# sunhub8_v1_0.net
KiCad netlist of a schematic drawn in EAGLE
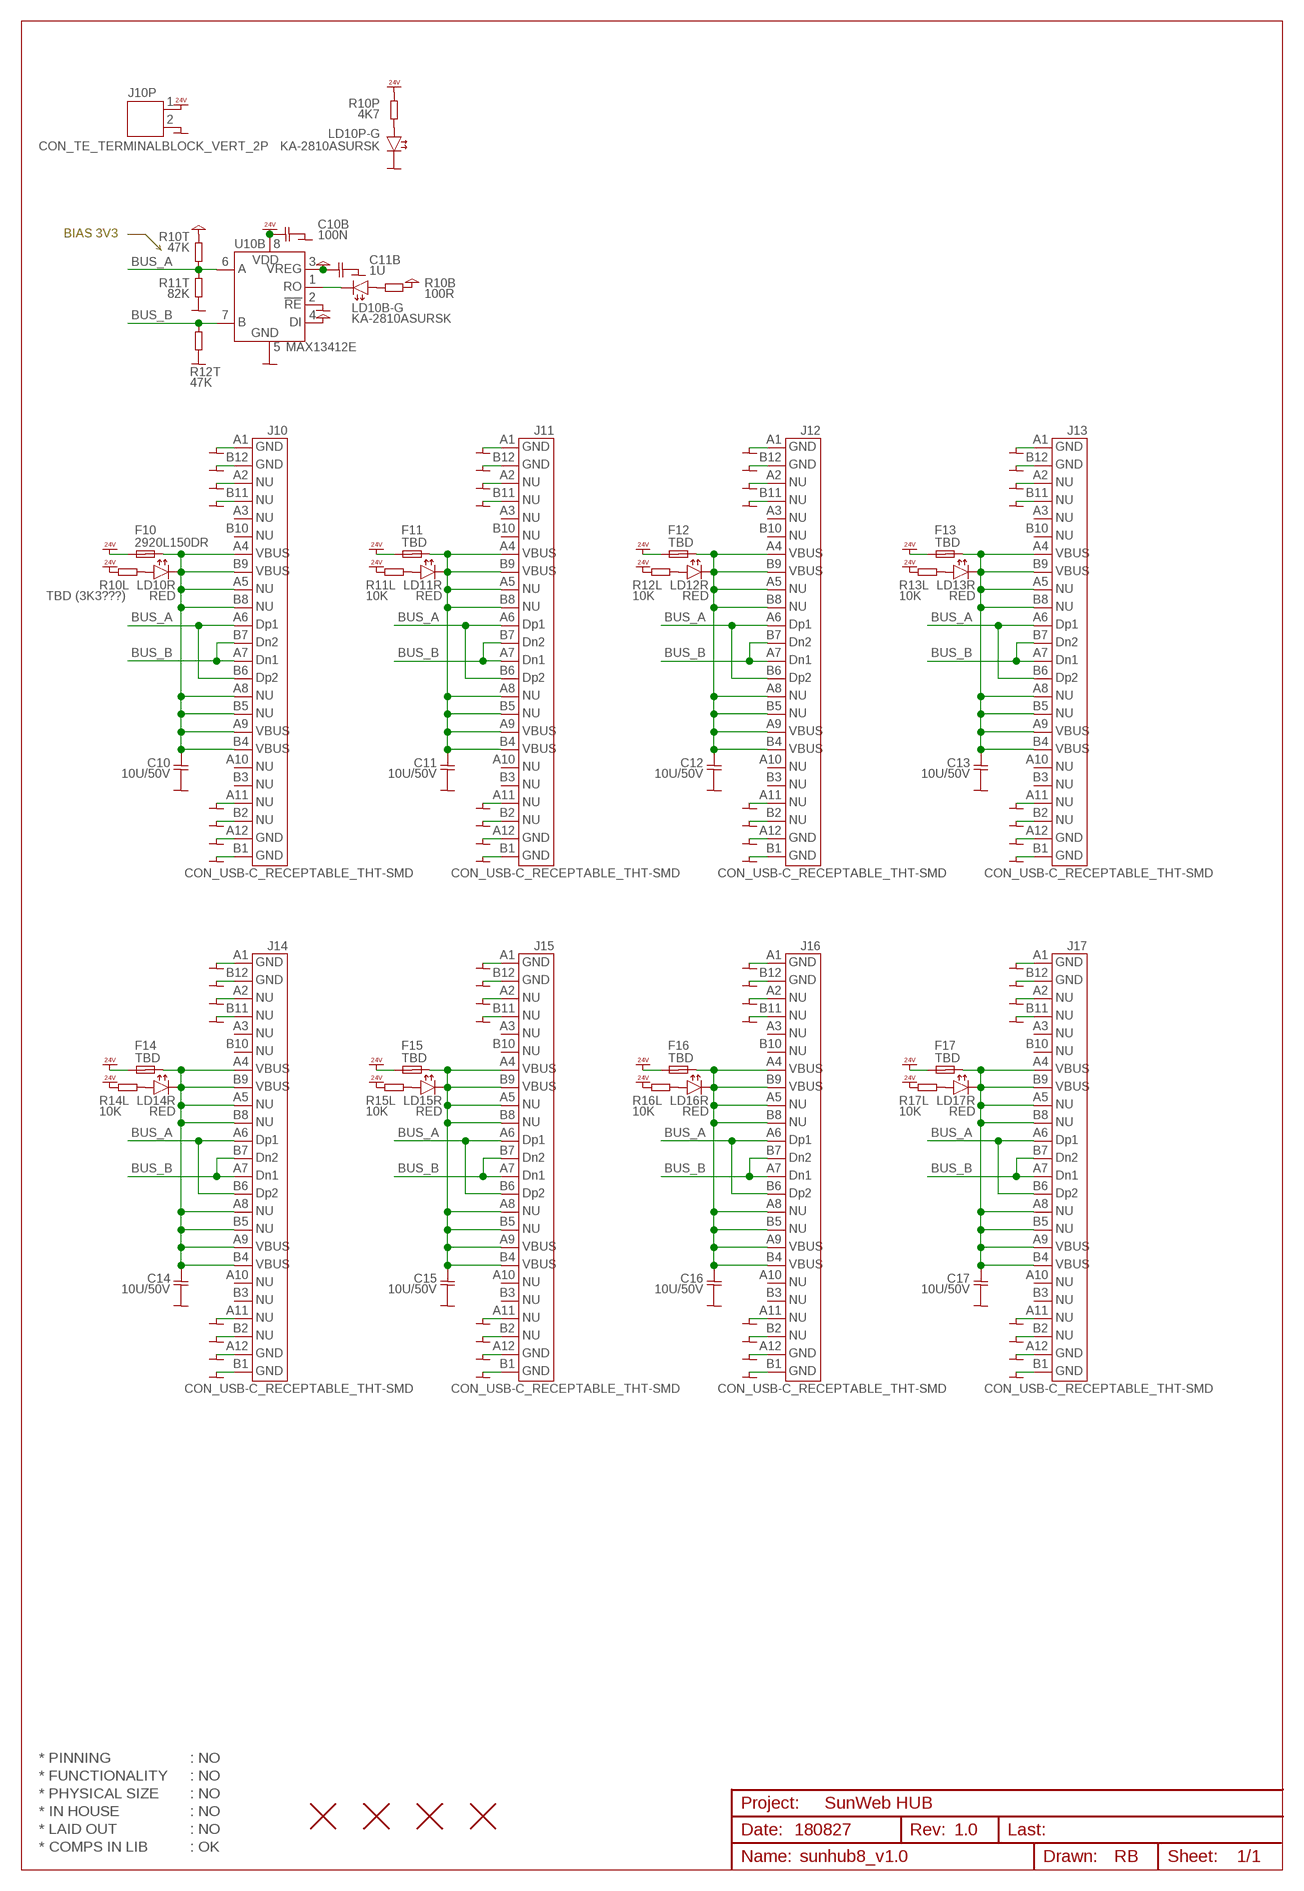
[diagram p0: schematic, sheet 1]

(export (version "E")
  (design (tool "Eeschema 10.0.6"))
  (components
    (comp (ref "C10")
      (value "10U/50V")
      (footprint "eagle-import:CAP1206")
      (libsource (lib "eagle-import") (part "CAP1206"))
    )
    (comp (ref "C10B")
      (value "100N")
      (footprint "eagle-import:CAP0603")
      (libsource (lib "eagle-import") (part "CAP0603"))
    )
    (comp (ref "C11")
      (value "10U/50V")
      (footprint "eagle-import:CAP1206")
      (libsource (lib "eagle-import") (part "CAP1206"))
    )
    (comp (ref "C11B")
      (value "1U")
      (footprint "eagle-import:CAP0603")
      (libsource (lib "eagle-import") (part "CAP0603"))
    )
    (comp (ref "C12")
      (value "10U/50V")
      (footprint "eagle-import:CAP1206")
      (libsource (lib "eagle-import") (part "CAP1206"))
    )
    (comp (ref "C13")
      (value "10U/50V")
      (footprint "eagle-import:CAP1206")
      (libsource (lib "eagle-import") (part "CAP1206"))
    )
    (comp (ref "C14")
      (value "10U/50V")
      (footprint "eagle-import:CAP1206")
      (libsource (lib "eagle-import") (part "CAP1206"))
    )
    (comp (ref "C15")
      (value "10U/50V")
      (footprint "eagle-import:CAP1206")
      (libsource (lib "eagle-import") (part "CAP1206"))
    )
    (comp (ref "C16")
      (value "10U/50V")
      (footprint "eagle-import:CAP1206")
      (libsource (lib "eagle-import") (part "CAP1206"))
    )
    (comp (ref "C17")
      (value "10U/50V")
      (footprint "eagle-import:CAP1206")
      (libsource (lib "eagle-import") (part "CAP1206"))
    )
    (comp (ref "F10")
      (value "2920L150DR")
      (footprint "eagle-import:POLYFUSE2920")
      (libsource (lib "eagle-import") (part "POLYFUSE2920"))
    )
    (comp (ref "F11")
      (value "TBD")
      (footprint "eagle-import:POLYFUSE2920")
      (libsource (lib "eagle-import") (part "POLYFUSE2920"))
    )
    (comp (ref "F12")
      (value "TBD")
      (footprint "eagle-import:POLYFUSE2920")
      (libsource (lib "eagle-import") (part "POLYFUSE2920"))
    )
    (comp (ref "F13")
      (value "TBD")
      (footprint "eagle-import:POLYFUSE2920")
      (libsource (lib "eagle-import") (part "POLYFUSE2920"))
    )
    (comp (ref "F14")
      (value "TBD")
      (footprint "eagle-import:POLYFUSE2920")
      (libsource (lib "eagle-import") (part "POLYFUSE2920"))
    )
    (comp (ref "F15")
      (value "TBD")
      (footprint "eagle-import:POLYFUSE2920")
      (libsource (lib "eagle-import") (part "POLYFUSE2920"))
    )
    (comp (ref "F16")
      (value "TBD")
      (footprint "eagle-import:POLYFUSE2920")
      (libsource (lib "eagle-import") (part "POLYFUSE2920"))
    )
    (comp (ref "F17")
      (value "TBD")
      (footprint "eagle-import:POLYFUSE2920")
      (libsource (lib "eagle-import") (part "POLYFUSE2920"))
    )
    (comp (ref "H1")
      (value "HOLE_NPTH_3.2MM")
      (footprint "eagle-import:HOLE_NPTH_3.2MM")
      (libsource (lib "eagle-import") (part "HOLE_NPTH_3.2MM"))
    )
    (comp (ref "H2")
      (value "HOLE_NPTH_3.2MM")
      (footprint "eagle-import:HOLE_NPTH_3.2MM")
      (libsource (lib "eagle-import") (part "HOLE_NPTH_3.2MM"))
    )
    (comp (ref "H3")
      (value "HOLE_NPTH_3.2MM")
      (footprint "eagle-import:HOLE_NPTH_3.2MM")
      (libsource (lib "eagle-import") (part "HOLE_NPTH_3.2MM"))
    )
    (comp (ref "H4")
      (value "HOLE_NPTH_3.2MM")
      (footprint "eagle-import:HOLE_NPTH_3.2MM")
      (libsource (lib "eagle-import") (part "HOLE_NPTH_3.2MM"))
    )
    (comp (ref "J10")
      (value "CON_USB-C_RECEPTABLE_THT-SMD")
      (footprint "eagle-import:CON_USB-C_RECEPTABLE_THT-SMD")
      (libsource (lib "eagle-import") (part "CON_USB-C_RECEPTABLE_THT-SMD"))
    )
    (comp (ref "J10P")
      (value "CON_TE_TERMINALBLOCK_VERT_2P")
      (footprint "eagle-import:CON_TE_TERMINALBLOCK_VERT_2P")
      (libsource (lib "eagle-import") (part "CON_TE_TERMINALBLOCK_VERT_2P"))
    )
    (comp (ref "J11")
      (value "CON_USB-C_RECEPTABLE_THT-SMD")
      (footprint "eagle-import:CON_USB-C_RECEPTABLE_THT-SMD")
      (libsource (lib "eagle-import") (part "CON_USB-C_RECEPTABLE_THT-SMD"))
    )
    (comp (ref "J12")
      (value "CON_USB-C_RECEPTABLE_THT-SMD")
      (footprint "eagle-import:CON_USB-C_RECEPTABLE_THT-SMD")
      (libsource (lib "eagle-import") (part "CON_USB-C_RECEPTABLE_THT-SMD"))
    )
    (comp (ref "J13")
      (value "CON_USB-C_RECEPTABLE_THT-SMD")
      (footprint "eagle-import:CON_USB-C_RECEPTABLE_THT-SMD")
      (libsource (lib "eagle-import") (part "CON_USB-C_RECEPTABLE_THT-SMD"))
    )
    (comp (ref "J14")
      (value "CON_USB-C_RECEPTABLE_THT-SMD")
      (footprint "eagle-import:CON_USB-C_RECEPTABLE_THT-SMD")
      (libsource (lib "eagle-import") (part "CON_USB-C_RECEPTABLE_THT-SMD"))
    )
    (comp (ref "J15")
      (value "CON_USB-C_RECEPTABLE_THT-SMD")
      (footprint "eagle-import:CON_USB-C_RECEPTABLE_THT-SMD")
      (libsource (lib "eagle-import") (part "CON_USB-C_RECEPTABLE_THT-SMD"))
    )
    (comp (ref "J16")
      (value "CON_USB-C_RECEPTABLE_THT-SMD")
      (footprint "eagle-import:CON_USB-C_RECEPTABLE_THT-SMD")
      (libsource (lib "eagle-import") (part "CON_USB-C_RECEPTABLE_THT-SMD"))
    )
    (comp (ref "J17")
      (value "CON_USB-C_RECEPTABLE_THT-SMD")
      (footprint "eagle-import:CON_USB-C_RECEPTABLE_THT-SMD")
      (libsource (lib "eagle-import") (part "CON_USB-C_RECEPTABLE_THT-SMD"))
    )
    (comp (ref "LD10B-G")
      (value "KA-2810ASURSK")
      (footprint "eagle-import:LED_SMD_ANGLE")
      (libsource (lib "eagle-import") (part "LED_SMD_ANGLE"))
    )
    (comp (ref "LD10P-G")
      (value "KA-2810ASURSK")
      (footprint "eagle-import:LED_SMD_ANGLE")
      (libsource (lib "eagle-import") (part "LED_SMD_ANGLE"))
    )
    (comp (ref "LD10R")
      (value "RED")
      (footprint "eagle-import:LED_SMD_ANGLE")
      (libsource (lib "eagle-import") (part "00-own_parts_LED_SMD_ANGLE"))
    )
    (comp (ref "LD11R")
      (value "RED")
      (footprint "eagle-import:LED_SMD_ANGLE")
      (libsource (lib "eagle-import") (part "00-own_parts_LED_SMD_ANGLE"))
    )
    (comp (ref "LD12R")
      (value "RED")
      (footprint "eagle-import:LED_SMD_ANGLE")
      (libsource (lib "eagle-import") (part "00-own_parts_LED_SMD_ANGLE"))
    )
    (comp (ref "LD13R")
      (value "RED")
      (footprint "eagle-import:LED_SMD_ANGLE")
      (libsource (lib "eagle-import") (part "00-own_parts_LED_SMD_ANGLE"))
    )
    (comp (ref "LD14R")
      (value "RED")
      (footprint "eagle-import:LED_SMD_ANGLE")
      (libsource (lib "eagle-import") (part "00-own_parts_LED_SMD_ANGLE"))
    )
    (comp (ref "LD15R")
      (value "RED")
      (footprint "eagle-import:LED_SMD_ANGLE")
      (libsource (lib "eagle-import") (part "00-own_parts_LED_SMD_ANGLE"))
    )
    (comp (ref "LD16R")
      (value "RED")
      (footprint "eagle-import:LED_SMD_ANGLE")
      (libsource (lib "eagle-import") (part "00-own_parts_LED_SMD_ANGLE"))
    )
    (comp (ref "LD17R")
      (value "RED")
      (footprint "eagle-import:LED_SMD_ANGLE")
      (libsource (lib "eagle-import") (part "00-own_parts_LED_SMD_ANGLE"))
    )
    (comp (ref "R10B")
      (value "100R")
      (footprint "eagle-import:RES0603")
      (libsource (lib "eagle-import") (part "RES0603"))
    )
    (comp (ref "R10L")
      (value "TBD (3K3???)")
      (footprint "eagle-import:RES0603")
      (libsource (lib "eagle-import") (part "RES0603"))
    )
    (comp (ref "R10P")
      (value "4K7")
      (footprint "eagle-import:RES0603")
      (libsource (lib "eagle-import") (part "RES0603"))
    )
    (comp (ref "R10T")
      (value "47K")
      (footprint "eagle-import:RES0603")
      (libsource (lib "eagle-import") (part "RES0603"))
    )
    (comp (ref "R11L")
      (value "10K")
      (footprint "eagle-import:RES0603")
      (libsource (lib "eagle-import") (part "RES0603"))
    )
    (comp (ref "R11T")
      (value "82K")
      (footprint "eagle-import:RES0603")
      (libsource (lib "eagle-import") (part "RES0603"))
    )
    (comp (ref "R12L")
      (value "10K")
      (footprint "eagle-import:RES0603")
      (libsource (lib "eagle-import") (part "RES0603"))
    )
    (comp (ref "R12T")
      (value "47K")
      (footprint "eagle-import:RES0603")
      (libsource (lib "eagle-import") (part "RES0603"))
    )
    (comp (ref "R13L")
      (value "10K")
      (footprint "eagle-import:RES0603")
      (libsource (lib "eagle-import") (part "RES0603"))
    )
    (comp (ref "R14L")
      (value "10K")
      (footprint "eagle-import:RES0603")
      (libsource (lib "eagle-import") (part "RES0603"))
    )
    (comp (ref "R15L")
      (value "10K")
      (footprint "eagle-import:RES0603")
      (libsource (lib "eagle-import") (part "RES0603"))
    )
    (comp (ref "R16L")
      (value "10K")
      (footprint "eagle-import:RES0603")
      (libsource (lib "eagle-import") (part "RES0603"))
    )
    (comp (ref "R17L")
      (value "10K")
      (footprint "eagle-import:RES0603")
      (libsource (lib "eagle-import") (part "RES0603"))
    )
    (comp (ref "U10B")
      (value "MAX13412E")
      (footprint "eagle-import:SO8")
      (libsource (lib "eagle-import") (part "MAX13412E"))
    )
  )
  (nets
    (net (code "1") (name "/BUS_A") (class "Default")
      (node (ref "J10") (pin "A6") (pinfunction "A6.DP1_A6") (pintype "passive"))
      (node (ref "J10") (pin "B6") (pinfunction "B6.DP2_B6") (pintype "passive"))
      (node (ref "J11") (pin "A6") (pinfunction "A6.DP1_A6") (pintype "passive"))
      (node (ref "J11") (pin "B6") (pinfunction "B6.DP2_B6") (pintype "passive"))
      (node (ref "J12") (pin "A6") (pinfunction "A6.DP1_A6") (pintype "passive"))
      (node (ref "J12") (pin "B6") (pinfunction "B6.DP2_B6") (pintype "passive"))
      (node (ref "J13") (pin "A6") (pinfunction "A6.DP1_A6") (pintype "passive"))
      (node (ref "J13") (pin "B6") (pinfunction "B6.DP2_B6") (pintype "passive"))
      (node (ref "J14") (pin "A6") (pinfunction "A6.DP1_A6") (pintype "passive"))
      (node (ref "J14") (pin "B6") (pinfunction "B6.DP2_B6") (pintype "passive"))
      (node (ref "J15") (pin "A6") (pinfunction "A6.DP1_A6") (pintype "passive"))
      (node (ref "J15") (pin "B6") (pinfunction "B6.DP2_B6") (pintype "passive"))
      (node (ref "J16") (pin "A6") (pinfunction "A6.DP1_A6") (pintype "passive"))
      (node (ref "J16") (pin "B6") (pinfunction "B6.DP2_B6") (pintype "passive"))
      (node (ref "J17") (pin "A6") (pinfunction "A6.DP1_A6") (pintype "passive"))
      (node (ref "J17") (pin "B6") (pinfunction "B6.DP2_B6") (pintype "passive"))
      (node (ref "R10T") (pin "2") (pinfunction "2_2") (pintype "passive"))
      (node (ref "R11T") (pin "1") (pinfunction "1_1") (pintype "passive"))
      (node (ref "U10B") (pin "6") (pinfunction "6.A_6") (pintype "passive"))
    )
    (net (code "2") (name "/BUS_B") (class "Default")
      (node (ref "J10") (pin "A7") (pinfunction "A7.DN1_A7") (pintype "passive"))
      (node (ref "J10") (pin "B7") (pinfunction "B7.DN2_B7") (pintype "passive"))
      (node (ref "J11") (pin "A7") (pinfunction "A7.DN1_A7") (pintype "passive"))
      (node (ref "J11") (pin "B7") (pinfunction "B7.DN2_B7") (pintype "passive"))
      (node (ref "J12") (pin "A7") (pinfunction "A7.DN1_A7") (pintype "passive"))
      (node (ref "J12") (pin "B7") (pinfunction "B7.DN2_B7") (pintype "passive"))
      (node (ref "J13") (pin "A7") (pinfunction "A7.DN1_A7") (pintype "passive"))
      (node (ref "J13") (pin "B7") (pinfunction "B7.DN2_B7") (pintype "passive"))
      (node (ref "J14") (pin "A7") (pinfunction "A7.DN1_A7") (pintype "passive"))
      (node (ref "J14") (pin "B7") (pinfunction "B7.DN2_B7") (pintype "passive"))
      (node (ref "J15") (pin "A7") (pinfunction "A7.DN1_A7") (pintype "passive"))
      (node (ref "J15") (pin "B7") (pinfunction "B7.DN2_B7") (pintype "passive"))
      (node (ref "J16") (pin "A7") (pinfunction "A7.DN1_A7") (pintype "passive"))
      (node (ref "J16") (pin "B7") (pinfunction "B7.DN2_B7") (pintype "passive"))
      (node (ref "J17") (pin "A7") (pinfunction "A7.DN1_A7") (pintype "passive"))
      (node (ref "J17") (pin "B7") (pinfunction "B7.DN2_B7") (pintype "passive"))
      (node (ref "R12T") (pin "1") (pinfunction "1_1") (pintype "passive"))
      (node (ref "U10B") (pin "7") (pinfunction "7.B_7") (pintype "passive"))
    )
    (net (code "3") (name "GND") (class "Default")
      (node (ref "C10") (pin "2") (pinfunction "2_2") (pintype "passive"))
      (node (ref "C10B") (pin "2") (pinfunction "2_2") (pintype "passive"))
      (node (ref "C11") (pin "2") (pinfunction "2_2") (pintype "passive"))
      (node (ref "C11B") (pin "2") (pinfunction "2_2") (pintype "passive"))
      (node (ref "C12") (pin "2") (pinfunction "2_2") (pintype "passive"))
      (node (ref "C13") (pin "2") (pinfunction "2_2") (pintype "passive"))
      (node (ref "C14") (pin "2") (pinfunction "2_2") (pintype "passive"))
      (node (ref "C15") (pin "2") (pinfunction "2_2") (pintype "passive"))
      (node (ref "C16") (pin "2") (pinfunction "2_2") (pintype "passive"))
      (node (ref "C17") (pin "2") (pinfunction "2_2") (pintype "passive"))
      (node (ref "J10") (pin "A1") (pinfunction "A1.GND_A1") (pintype "passive"))
      (node (ref "J10") (pin "A11") (pinfunction "A11.NU_A11") (pintype "passive"))
      (node (ref "J10") (pin "A12") (pinfunction "A12.GND_A12") (pintype "passive"))
      (node (ref "J10") (pin "A2") (pinfunction "A2.NU_A2") (pintype "passive"))
      (node (ref "J10") (pin "B1") (pinfunction "B1.GND_B1") (pintype "passive"))
      (node (ref "J10") (pin "B11") (pinfunction "B11.NU_B11") (pintype "passive"))
      (node (ref "J10") (pin "B12") (pinfunction "B12.GND_B12") (pintype "passive"))
      (node (ref "J10") (pin "B2") (pinfunction "B2.NU_B2") (pintype "passive"))
      (node (ref "J10P") (pin "2") (pinfunction "2_2") (pintype "passive"))
      (node (ref "J11") (pin "A1") (pinfunction "A1.GND_A1") (pintype "passive"))
      (node (ref "J11") (pin "A11") (pinfunction "A11.NU_A11") (pintype "passive"))
      (node (ref "J11") (pin "A12") (pinfunction "A12.GND_A12") (pintype "passive"))
      (node (ref "J11") (pin "A2") (pinfunction "A2.NU_A2") (pintype "passive"))
      (node (ref "J11") (pin "B1") (pinfunction "B1.GND_B1") (pintype "passive"))
      (node (ref "J11") (pin "B11") (pinfunction "B11.NU_B11") (pintype "passive"))
      (node (ref "J11") (pin "B12") (pinfunction "B12.GND_B12") (pintype "passive"))
      (node (ref "J11") (pin "B2") (pinfunction "B2.NU_B2") (pintype "passive"))
      (node (ref "J12") (pin "A1") (pinfunction "A1.GND_A1") (pintype "passive"))
      (node (ref "J12") (pin "A11") (pinfunction "A11.NU_A11") (pintype "passive"))
      (node (ref "J12") (pin "A12") (pinfunction "A12.GND_A12") (pintype "passive"))
      (node (ref "J12") (pin "A2") (pinfunction "A2.NU_A2") (pintype "passive"))
      (node (ref "J12") (pin "B1") (pinfunction "B1.GND_B1") (pintype "passive"))
      (node (ref "J12") (pin "B11") (pinfunction "B11.NU_B11") (pintype "passive"))
      (node (ref "J12") (pin "B12") (pinfunction "B12.GND_B12") (pintype "passive"))
      (node (ref "J12") (pin "B2") (pinfunction "B2.NU_B2") (pintype "passive"))
      (node (ref "J13") (pin "A1") (pinfunction "A1.GND_A1") (pintype "passive"))
      (node (ref "J13") (pin "A11") (pinfunction "A11.NU_A11") (pintype "passive"))
      (node (ref "J13") (pin "A12") (pinfunction "A12.GND_A12") (pintype "passive"))
      (node (ref "J13") (pin "A2") (pinfunction "A2.NU_A2") (pintype "passive"))
      (node (ref "J13") (pin "B1") (pinfunction "B1.GND_B1") (pintype "passive"))
      (node (ref "J13") (pin "B11") (pinfunction "B11.NU_B11") (pintype "passive"))
      (node (ref "J13") (pin "B12") (pinfunction "B12.GND_B12") (pintype "passive"))
      (node (ref "J13") (pin "B2") (pinfunction "B2.NU_B2") (pintype "passive"))
      (node (ref "J14") (pin "A1") (pinfunction "A1.GND_A1") (pintype "passive"))
      (node (ref "J14") (pin "A11") (pinfunction "A11.NU_A11") (pintype "passive"))
      (node (ref "J14") (pin "A12") (pinfunction "A12.GND_A12") (pintype "passive"))
      (node (ref "J14") (pin "A2") (pinfunction "A2.NU_A2") (pintype "passive"))
      (node (ref "J14") (pin "B1") (pinfunction "B1.GND_B1") (pintype "passive"))
      (node (ref "J14") (pin "B11") (pinfunction "B11.NU_B11") (pintype "passive"))
      (node (ref "J14") (pin "B12") (pinfunction "B12.GND_B12") (pintype "passive"))
      (node (ref "J14") (pin "B2") (pinfunction "B2.NU_B2") (pintype "passive"))
      (node (ref "J15") (pin "A1") (pinfunction "A1.GND_A1") (pintype "passive"))
      (node (ref "J15") (pin "A11") (pinfunction "A11.NU_A11") (pintype "passive"))
      (node (ref "J15") (pin "A12") (pinfunction "A12.GND_A12") (pintype "passive"))
      (node (ref "J15") (pin "A2") (pinfunction "A2.NU_A2") (pintype "passive"))
      (node (ref "J15") (pin "B1") (pinfunction "B1.GND_B1") (pintype "passive"))
      (node (ref "J15") (pin "B11") (pinfunction "B11.NU_B11") (pintype "passive"))
      (node (ref "J15") (pin "B12") (pinfunction "B12.GND_B12") (pintype "passive"))
      (node (ref "J15") (pin "B2") (pinfunction "B2.NU_B2") (pintype "passive"))
      (node (ref "J16") (pin "A1") (pinfunction "A1.GND_A1") (pintype "passive"))
      (node (ref "J16") (pin "A11") (pinfunction "A11.NU_A11") (pintype "passive"))
      (node (ref "J16") (pin "A12") (pinfunction "A12.GND_A12") (pintype "passive"))
      (node (ref "J16") (pin "A2") (pinfunction "A2.NU_A2") (pintype "passive"))
      (node (ref "J16") (pin "B1") (pinfunction "B1.GND_B1") (pintype "passive"))
      (node (ref "J16") (pin "B11") (pinfunction "B11.NU_B11") (pintype "passive"))
      (node (ref "J16") (pin "B12") (pinfunction "B12.GND_B12") (pintype "passive"))
      (node (ref "J16") (pin "B2") (pinfunction "B2.NU_B2") (pintype "passive"))
      (node (ref "J17") (pin "A1") (pinfunction "A1.GND_A1") (pintype "passive"))
      (node (ref "J17") (pin "A11") (pinfunction "A11.NU_A11") (pintype "passive"))
      (node (ref "J17") (pin "A12") (pinfunction "A12.GND_A12") (pintype "passive"))
      (node (ref "J17") (pin "A2") (pinfunction "A2.NU_A2") (pintype "passive"))
      (node (ref "J17") (pin "B1") (pinfunction "B1.GND_B1") (pintype "passive"))
      (node (ref "J17") (pin "B11") (pinfunction "B11.NU_B11") (pintype "passive"))
      (node (ref "J17") (pin "B12") (pinfunction "B12.GND_B12") (pintype "passive"))
      (node (ref "J17") (pin "B2") (pinfunction "B2.NU_B2") (pintype "passive"))
      (node (ref "LD10P-G") (pin "C") (pinfunction "C_C") (pintype "passive"))
      (node (ref "R11T") (pin "2") (pinfunction "2_2") (pintype "passive"))
      (node (ref "R12T") (pin "2") (pinfunction "2_2") (pintype "passive"))
      (node (ref "U10B") (pin "2") (pinfunction "2.~{RE}_2") (pintype "passive"))
      (node (ref "U10B") (pin "5") (pinfunction "5.GND_5") (pintype "passive"))
    )
    (net (code "4") (name "Net-(F10-P$2)") (class "Default")
      (node (ref "C10") (pin "1") (pinfunction "1_1") (pintype "passive"))
      (node (ref "F10") (pin "2") (pinfunction "P$2_2") (pintype "passive"))
      (node (ref "J10") (pin "A4") (pinfunction "A4.VBUS_A4") (pintype "passive"))
      (node (ref "J10") (pin "A5") (pinfunction "A5.NU_A5") (pintype "passive"))
      (node (ref "J10") (pin "A8") (pinfunction "A8.NU_A8") (pintype "passive"))
      (node (ref "J10") (pin "A9") (pinfunction "A9.VBUS_A9") (pintype "passive"))
      (node (ref "J10") (pin "B4") (pinfunction "B4.VBUS_B4") (pintype "passive"))
      (node (ref "J10") (pin "B5") (pinfunction "B5.NU_B5") (pintype "passive"))
      (node (ref "J10") (pin "B8") (pinfunction "B8.NU_B8") (pintype "passive"))
      (node (ref "J10") (pin "B9") (pinfunction "B9.VBUS_B9") (pintype "passive"))
      (node (ref "LD10R") (pin "C") (pinfunction "C_C") (pintype "passive"))
    )
    (net (code "5") (name "Net-(F11-P$2)") (class "Default")
      (node (ref "C11") (pin "1") (pinfunction "1_1") (pintype "passive"))
      (node (ref "F11") (pin "2") (pinfunction "P$2_2") (pintype "passive"))
      (node (ref "J11") (pin "A4") (pinfunction "A4.VBUS_A4") (pintype "passive"))
      (node (ref "J11") (pin "A5") (pinfunction "A5.NU_A5") (pintype "passive"))
      (node (ref "J11") (pin "A8") (pinfunction "A8.NU_A8") (pintype "passive"))
      (node (ref "J11") (pin "A9") (pinfunction "A9.VBUS_A9") (pintype "passive"))
      (node (ref "J11") (pin "B4") (pinfunction "B4.VBUS_B4") (pintype "passive"))
      (node (ref "J11") (pin "B5") (pinfunction "B5.NU_B5") (pintype "passive"))
      (node (ref "J11") (pin "B8") (pinfunction "B8.NU_B8") (pintype "passive"))
      (node (ref "J11") (pin "B9") (pinfunction "B9.VBUS_B9") (pintype "passive"))
      (node (ref "LD11R") (pin "C") (pinfunction "C_C") (pintype "passive"))
    )
    (net (code "6") (name "Net-(F12-P$2)") (class "Default")
      (node (ref "C12") (pin "1") (pinfunction "1_1") (pintype "passive"))
      (node (ref "F12") (pin "2") (pinfunction "P$2_2") (pintype "passive"))
      (node (ref "J12") (pin "A4") (pinfunction "A4.VBUS_A4") (pintype "passive"))
      (node (ref "J12") (pin "A5") (pinfunction "A5.NU_A5") (pintype "passive"))
      (node (ref "J12") (pin "A8") (pinfunction "A8.NU_A8") (pintype "passive"))
      (node (ref "J12") (pin "A9") (pinfunction "A9.VBUS_A9") (pintype "passive"))
      (node (ref "J12") (pin "B4") (pinfunction "B4.VBUS_B4") (pintype "passive"))
      (node (ref "J12") (pin "B5") (pinfunction "B5.NU_B5") (pintype "passive"))
      (node (ref "J12") (pin "B8") (pinfunction "B8.NU_B8") (pintype "passive"))
      (node (ref "J12") (pin "B9") (pinfunction "B9.VBUS_B9") (pintype "passive"))
      (node (ref "LD12R") (pin "C") (pinfunction "C_C") (pintype "passive"))
    )
    (net (code "7") (name "Net-(F13-P$2)") (class "Default")
      (node (ref "C13") (pin "1") (pinfunction "1_1") (pintype "passive"))
      (node (ref "F13") (pin "2") (pinfunction "P$2_2") (pintype "passive"))
      (node (ref "J13") (pin "A4") (pinfunction "A4.VBUS_A4") (pintype "passive"))
      (node (ref "J13") (pin "A5") (pinfunction "A5.NU_A5") (pintype "passive"))
      (node (ref "J13") (pin "A8") (pinfunction "A8.NU_A8") (pintype "passive"))
      (node (ref "J13") (pin "A9") (pinfunction "A9.VBUS_A9") (pintype "passive"))
      (node (ref "J13") (pin "B4") (pinfunction "B4.VBUS_B4") (pintype "passive"))
      (node (ref "J13") (pin "B5") (pinfunction "B5.NU_B5") (pintype "passive"))
      (node (ref "J13") (pin "B8") (pinfunction "B8.NU_B8") (pintype "passive"))
      (node (ref "J13") (pin "B9") (pinfunction "B9.VBUS_B9") (pintype "passive"))
      (node (ref "LD13R") (pin "C") (pinfunction "C_C") (pintype "passive"))
    )
    (net (code "8") (name "Net-(F14-P$2)") (class "Default")
      (node (ref "C14") (pin "1") (pinfunction "1_1") (pintype "passive"))
      (node (ref "F14") (pin "2") (pinfunction "P$2_2") (pintype "passive"))
      (node (ref "J14") (pin "A4") (pinfunction "A4.VBUS_A4") (pintype "passive"))
      (node (ref "J14") (pin "A5") (pinfunction "A5.NU_A5") (pintype "passive"))
      (node (ref "J14") (pin "A8") (pinfunction "A8.NU_A8") (pintype "passive"))
      (node (ref "J14") (pin "A9") (pinfunction "A9.VBUS_A9") (pintype "passive"))
      (node (ref "J14") (pin "B4") (pinfunction "B4.VBUS_B4") (pintype "passive"))
      (node (ref "J14") (pin "B5") (pinfunction "B5.NU_B5") (pintype "passive"))
      (node (ref "J14") (pin "B8") (pinfunction "B8.NU_B8") (pintype "passive"))
      (node (ref "J14") (pin "B9") (pinfunction "B9.VBUS_B9") (pintype "passive"))
      (node (ref "LD14R") (pin "C") (pinfunction "C_C") (pintype "passive"))
    )
    (net (code "9") (name "Net-(F15-P$2)") (class "Default")
      (node (ref "C15") (pin "1") (pinfunction "1_1") (pintype "passive"))
      (node (ref "F15") (pin "2") (pinfunction "P$2_2") (pintype "passive"))
      (node (ref "J15") (pin "A4") (pinfunction "A4.VBUS_A4") (pintype "passive"))
      (node (ref "J15") (pin "A5") (pinfunction "A5.NU_A5") (pintype "passive"))
      (node (ref "J15") (pin "A8") (pinfunction "A8.NU_A8") (pintype "passive"))
      (node (ref "J15") (pin "A9") (pinfunction "A9.VBUS_A9") (pintype "passive"))
      (node (ref "J15") (pin "B4") (pinfunction "B4.VBUS_B4") (pintype "passive"))
      (node (ref "J15") (pin "B5") (pinfunction "B5.NU_B5") (pintype "passive"))
      (node (ref "J15") (pin "B8") (pinfunction "B8.NU_B8") (pintype "passive"))
      (node (ref "J15") (pin "B9") (pinfunction "B9.VBUS_B9") (pintype "passive"))
      (node (ref "LD15R") (pin "C") (pinfunction "C_C") (pintype "passive"))
    )
    (net (code "10") (name "Net-(F16-P$2)") (class "Default")
      (node (ref "C16") (pin "1") (pinfunction "1_1") (pintype "passive"))
      (node (ref "F16") (pin "2") (pinfunction "P$2_2") (pintype "passive"))
      (node (ref "J16") (pin "A4") (pinfunction "A4.VBUS_A4") (pintype "passive"))
      (node (ref "J16") (pin "A5") (pinfunction "A5.NU_A5") (pintype "passive"))
      (node (ref "J16") (pin "A8") (pinfunction "A8.NU_A8") (pintype "passive"))
      (node (ref "J16") (pin "A9") (pinfunction "A9.VBUS_A9") (pintype "passive"))
      (node (ref "J16") (pin "B4") (pinfunction "B4.VBUS_B4") (pintype "passive"))
      (node (ref "J16") (pin "B5") (pinfunction "B5.NU_B5") (pintype "passive"))
      (node (ref "J16") (pin "B8") (pinfunction "B8.NU_B8") (pintype "passive"))
      (node (ref "J16") (pin "B9") (pinfunction "B9.VBUS_B9") (pintype "passive"))
      (node (ref "LD16R") (pin "C") (pinfunction "C_C") (pintype "passive"))
    )
    (net (code "11") (name "Net-(F17-P$2)") (class "Default")
      (node (ref "C17") (pin "1") (pinfunction "1_1") (pintype "passive"))
      (node (ref "F17") (pin "2") (pinfunction "P$2_2") (pintype "passive"))
      (node (ref "J17") (pin "A4") (pinfunction "A4.VBUS_A4") (pintype "passive"))
      (node (ref "J17") (pin "A5") (pinfunction "A5.NU_A5") (pintype "passive"))
      (node (ref "J17") (pin "A8") (pinfunction "A8.NU_A8") (pintype "passive"))
      (node (ref "J17") (pin "A9") (pinfunction "A9.VBUS_A9") (pintype "passive"))
      (node (ref "J17") (pin "B4") (pinfunction "B4.VBUS_B4") (pintype "passive"))
      (node (ref "J17") (pin "B5") (pinfunction "B5.NU_B5") (pintype "passive"))
      (node (ref "J17") (pin "B8") (pinfunction "B8.NU_B8") (pintype "passive"))
      (node (ref "J17") (pin "B9") (pinfunction "B9.VBUS_B9") (pintype "passive"))
      (node (ref "LD17R") (pin "C") (pinfunction "C_C") (pintype "passive"))
    )
    (net (code "12") (name "Net-(LD10B-G-PadA)") (class "Default")
      (node (ref "LD10B-G") (pin "A") (pinfunction "A_A") (pintype "passive"))
      (node (ref "R10B") (pin "1") (pinfunction "1_1") (pintype "passive"))
    )
    (net (code "13") (name "Net-(LD10P-G-PadA)") (class "Default")
      (node (ref "LD10P-G") (pin "A") (pinfunction "A_A") (pintype "passive"))
      (node (ref "R10P") (pin "2") (pinfunction "2_2") (pintype "passive"))
    )
    (net (code "14") (name "Net-(LD10R-PadA)") (class "Default")
      (node (ref "LD10R") (pin "A") (pinfunction "A_A") (pintype "passive"))
      (node (ref "R10L") (pin "2") (pinfunction "2_2") (pintype "passive"))
    )
    (net (code "15") (name "Net-(LD11R-PadA)") (class "Default")
      (node (ref "LD11R") (pin "A") (pinfunction "A_A") (pintype "passive"))
      (node (ref "R11L") (pin "2") (pinfunction "2_2") (pintype "passive"))
    )
    (net (code "16") (name "Net-(LD12R-PadA)") (class "Default")
      (node (ref "LD12R") (pin "A") (pinfunction "A_A") (pintype "passive"))
      (node (ref "R12L") (pin "2") (pinfunction "2_2") (pintype "passive"))
    )
    (net (code "17") (name "Net-(LD13R-PadA)") (class "Default")
      (node (ref "LD13R") (pin "A") (pinfunction "A_A") (pintype "passive"))
      (node (ref "R13L") (pin "2") (pinfunction "2_2") (pintype "passive"))
    )
    (net (code "18") (name "Net-(LD14R-PadA)") (class "Default")
      (node (ref "LD14R") (pin "A") (pinfunction "A_A") (pintype "passive"))
      (node (ref "R14L") (pin "2") (pinfunction "2_2") (pintype "passive"))
    )
    (net (code "19") (name "Net-(LD15R-PadA)") (class "Default")
      (node (ref "LD15R") (pin "A") (pinfunction "A_A") (pintype "passive"))
      (node (ref "R15L") (pin "2") (pinfunction "2_2") (pintype "passive"))
    )
    (net (code "20") (name "Net-(LD16R-PadA)") (class "Default")
      (node (ref "LD16R") (pin "A") (pinfunction "A_A") (pintype "passive"))
      (node (ref "R16L") (pin "2") (pinfunction "2_2") (pintype "passive"))
    )
    (net (code "21") (name "Net-(LD17R-PadA)") (class "Default")
      (node (ref "LD17R") (pin "A") (pinfunction "A_A") (pintype "passive"))
      (node (ref "R17L") (pin "2") (pinfunction "2_2") (pintype "passive"))
    )
    (net (code "22") (name "Net-(U10B-1.RO)") (class "Default")
      (node (ref "LD10B-G") (pin "C") (pinfunction "C_C") (pintype "passive"))
      (node (ref "U10B") (pin "1") (pinfunction "1.RO_1") (pintype "passive"))
    )
    (net (code "23") (name "VCC") (class "Default")
      (node (ref "C11B") (pin "1") (pinfunction "1_1") (pintype "passive"))
      (node (ref "R10B") (pin "2") (pinfunction "2_2") (pintype "passive"))
      (node (ref "R10T") (pin "1") (pinfunction "1_1") (pintype "passive"))
      (node (ref "U10B") (pin "3") (pinfunction "3.DE_3") (pintype "passive"))
      (node (ref "U10B") (pin "4") (pinfunction "4.DI_4") (pintype "passive"))
    )
    (net (code "24") (name "VCC_24V") (class "Default")
      (node (ref "C10B") (pin "1") (pinfunction "1_1") (pintype "passive"))
      (node (ref "F10") (pin "1") (pinfunction "P$1_1") (pintype "passive"))
      (node (ref "F11") (pin "1") (pinfunction "P$1_1") (pintype "passive"))
      (node (ref "F12") (pin "1") (pinfunction "P$1_1") (pintype "passive"))
      (node (ref "F13") (pin "1") (pinfunction "P$1_1") (pintype "passive"))
      (node (ref "F14") (pin "1") (pinfunction "P$1_1") (pintype "passive"))
      (node (ref "F15") (pin "1") (pinfunction "P$1_1") (pintype "passive"))
      (node (ref "F16") (pin "1") (pinfunction "P$1_1") (pintype "passive"))
      (node (ref "F17") (pin "1") (pinfunction "P$1_1") (pintype "passive"))
      (node (ref "J10P") (pin "1") (pinfunction "1_1") (pintype "passive"))
      (node (ref "R10L") (pin "1") (pinfunction "1_1") (pintype "passive"))
      (node (ref "R10P") (pin "1") (pinfunction "1_1") (pintype "passive"))
      (node (ref "R11L") (pin "1") (pinfunction "1_1") (pintype "passive"))
      (node (ref "R12L") (pin "1") (pinfunction "1_1") (pintype "passive"))
      (node (ref "R13L") (pin "1") (pinfunction "1_1") (pintype "passive"))
      (node (ref "R14L") (pin "1") (pinfunction "1_1") (pintype "passive"))
      (node (ref "R15L") (pin "1") (pinfunction "1_1") (pintype "passive"))
      (node (ref "R16L") (pin "1") (pinfunction "1_1") (pintype "passive"))
      (node (ref "R17L") (pin "1") (pinfunction "1_1") (pintype "passive"))
      (node (ref "U10B") (pin "8") (pinfunction "8.VDD_8") (pintype "passive"))
    )
    (net (code "25") (name "unconnected-(J10-A3.NU-PadA3)") (class "Default")
      (node (ref "J10") (pin "A3") (pinfunction "A3.NU_A3") (pintype "passive"))
    )
    (net (code "26") (name "unconnected-(J10-A10.NU-PadA10)") (class "Default")
      (node (ref "J10") (pin "A10") (pinfunction "A10.NU_A10") (pintype "passive"))
    )
    (net (code "27") (name "unconnected-(J10-B3.NU-PadB3)") (class "Default")
      (node (ref "J10") (pin "B3") (pinfunction "B3.NU_B3") (pintype "passive"))
    )
    (net (code "28") (name "unconnected-(J10-B10.NU-PadB10)") (class "Default")
      (node (ref "J10") (pin "B10") (pinfunction "B10.NU_B10") (pintype "passive"))
    )
    (net (code "29") (name "unconnected-(J11-A3.NU-PadA3)") (class "Default")
      (node (ref "J11") (pin "A3") (pinfunction "A3.NU_A3") (pintype "passive"))
    )
    (net (code "30") (name "unconnected-(J11-A10.NU-PadA10)") (class "Default")
      (node (ref "J11") (pin "A10") (pinfunction "A10.NU_A10") (pintype "passive"))
    )
    (net (code "31") (name "unconnected-(J11-B3.NU-PadB3)") (class "Default")
      (node (ref "J11") (pin "B3") (pinfunction "B3.NU_B3") (pintype "passive"))
    )
    (net (code "32") (name "unconnected-(J11-B10.NU-PadB10)") (class "Default")
      (node (ref "J11") (pin "B10") (pinfunction "B10.NU_B10") (pintype "passive"))
    )
    (net (code "33") (name "unconnected-(J12-A3.NU-PadA3)") (class "Default")
      (node (ref "J12") (pin "A3") (pinfunction "A3.NU_A3") (pintype "passive"))
    )
    (net (code "34") (name "unconnected-(J12-A10.NU-PadA10)") (class "Default")
      (node (ref "J12") (pin "A10") (pinfunction "A10.NU_A10") (pintype "passive"))
    )
    (net (code "35") (name "unconnected-(J12-B3.NU-PadB3)") (class "Default")
      (node (ref "J12") (pin "B3") (pinfunction "B3.NU_B3") (pintype "passive"))
    )
    (net (code "36") (name "unconnected-(J12-B10.NU-PadB10)") (class "Default")
      (node (ref "J12") (pin "B10") (pinfunction "B10.NU_B10") (pintype "passive"))
    )
    (net (code "37") (name "unconnected-(J13-A3.NU-PadA3)") (class "Default")
      (node (ref "J13") (pin "A3") (pinfunction "A3.NU_A3") (pintype "passive"))
    )
    (net (code "38") (name "unconnected-(J13-A10.NU-PadA10)") (class "Default")
      (node (ref "J13") (pin "A10") (pinfunction "A10.NU_A10") (pintype "passive"))
    )
    (net (code "39") (name "unconnected-(J13-B3.NU-PadB3)") (class "Default")
      (node (ref "J13") (pin "B3") (pinfunction "B3.NU_B3") (pintype "passive"))
    )
    (net (code "40") (name "unconnected-(J13-B10.NU-PadB10)") (class "Default")
      (node (ref "J13") (pin "B10") (pinfunction "B10.NU_B10") (pintype "passive"))
    )
    (net (code "41") (name "unconnected-(J14-A3.NU-PadA3)") (class "Default")
      (node (ref "J14") (pin "A3") (pinfunction "A3.NU_A3") (pintype "passive"))
    )
    (net (code "42") (name "unconnected-(J14-A10.NU-PadA10)") (class "Default")
      (node (ref "J14") (pin "A10") (pinfunction "A10.NU_A10") (pintype "passive"))
    )
    (net (code "43") (name "unconnected-(J14-B3.NU-PadB3)") (class "Default")
      (node (ref "J14") (pin "B3") (pinfunction "B3.NU_B3") (pintype "passive"))
    )
    (net (code "44") (name "unconnected-(J14-B10.NU-PadB10)") (class "Default")
      (node (ref "J14") (pin "B10") (pinfunction "B10.NU_B10") (pintype "passive"))
    )
    (net (code "45") (name "unconnected-(J15-A3.NU-PadA3)") (class "Default")
      (node (ref "J15") (pin "A3") (pinfunction "A3.NU_A3") (pintype "passive"))
    )
    (net (code "46") (name "unconnected-(J15-A10.NU-PadA10)") (class "Default")
      (node (ref "J15") (pin "A10") (pinfunction "A10.NU_A10") (pintype "passive"))
    )
    (net (code "47") (name "unconnected-(J15-B3.NU-PadB3)") (class "Default")
      (node (ref "J15") (pin "B3") (pinfunction "B3.NU_B3") (pintype "passive"))
    )
    (net (code "48") (name "unconnected-(J15-B10.NU-PadB10)") (class "Default")
      (node (ref "J15") (pin "B10") (pinfunction "B10.NU_B10") (pintype "passive"))
    )
    (net (code "49") (name "unconnected-(J16-A3.NU-PadA3)") (class "Default")
      (node (ref "J16") (pin "A3") (pinfunction "A3.NU_A3") (pintype "passive"))
    )
    (net (code "50") (name "unconnected-(J16-A10.NU-PadA10)") (class "Default")
      (node (ref "J16") (pin "A10") (pinfunction "A10.NU_A10") (pintype "passive"))
    )
    (net (code "51") (name "unconnected-(J16-B3.NU-PadB3)") (class "Default")
      (node (ref "J16") (pin "B3") (pinfunction "B3.NU_B3") (pintype "passive"))
    )
    (net (code "52") (name "unconnected-(J16-B10.NU-PadB10)") (class "Default")
      (node (ref "J16") (pin "B10") (pinfunction "B10.NU_B10") (pintype "passive"))
    )
    (net (code "53") (name "unconnected-(J17-A3.NU-PadA3)") (class "Default")
      (node (ref "J17") (pin "A3") (pinfunction "A3.NU_A3") (pintype "passive"))
    )
    (net (code "54") (name "unconnected-(J17-A10.NU-PadA10)") (class "Default")
      (node (ref "J17") (pin "A10") (pinfunction "A10.NU_A10") (pintype "passive"))
    )
    (net (code "55") (name "unconnected-(J17-B3.NU-PadB3)") (class "Default")
      (node (ref "J17") (pin "B3") (pinfunction "B3.NU_B3") (pintype "passive"))
    )
    (net (code "56") (name "unconnected-(J17-B10.NU-PadB10)") (class "Default")
      (node (ref "J17") (pin "B10") (pinfunction "B10.NU_B10") (pintype "passive"))
    )
  )
)
